# SDRAM.net
KiCad netlist of a schematic drawn in Altium Designer
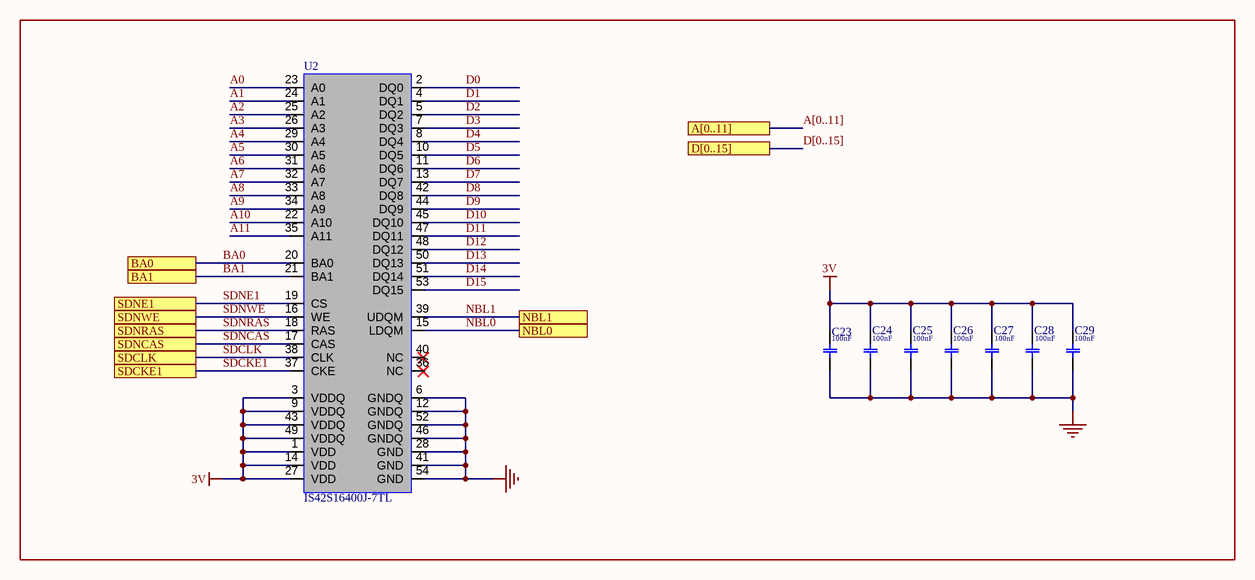
[diagram p0: SDRAM.SchDoc]

(export (version "E")
  (design (tool "Eeschema 10.0.6"))
  (components
    (comp (ref "C23")
      (value "100nF")
      (footprint "CAP-0402")
      (description "Multilayer Ceramic Capacitor, 0.1 uF, 25 V, ± 10%, X7R, 0402 [1005 Metric]")
      (fields
        (field (name "MANUFACTURER") "Yageo")
        (field (name "MANUFACTURER PART NUMBER") "CC0402KRX7R7BB104")
      )
      (libsource (lib "STM32") (part "CAP CER 100nF 16V X7R 0402"))
    )
    (comp (ref "C24")
      (value "100nF")
      (footprint "CAP-0402")
      (description "Multilayer Ceramic Capacitor, 0.1 uF, 25 V, ± 10%, X7R, 0402 [1005 Metric]")
      (fields
        (field (name "MANUFACTURER") "Yageo")
        (field (name "MANUFACTURER PART NUMBER") "CC0402KRX7R7BB104")
      )
      (libsource (lib "STM32") (part "CAP CER 100nF 16V X7R 0402"))
    )
    (comp (ref "C25")
      (value "100nF")
      (footprint "CAP-0402")
      (description "Multilayer Ceramic Capacitor, 0.1 uF, 25 V, ± 10%, X7R, 0402 [1005 Metric]")
      (fields
        (field (name "MANUFACTURER") "Yageo")
        (field (name "MANUFACTURER PART NUMBER") "CC0402KRX7R7BB104")
      )
      (libsource (lib "STM32") (part "CAP CER 100nF 16V X7R 0402"))
    )
    (comp (ref "C26")
      (value "100nF")
      (footprint "CAP-0402")
      (description "Multilayer Ceramic Capacitor, 0.1 uF, 25 V, ± 10%, X7R, 0402 [1005 Metric]")
      (fields
        (field (name "MANUFACTURER") "Yageo")
        (field (name "MANUFACTURER PART NUMBER") "CC0402KRX7R7BB104")
      )
      (libsource (lib "STM32") (part "CAP CER 100nF 16V X7R 0402"))
    )
    (comp (ref "C27")
      (value "100nF")
      (footprint "CAP-0402")
      (description "Multilayer Ceramic Capacitor, 0.1 uF, 25 V, ± 10%, X7R, 0402 [1005 Metric]")
      (fields
        (field (name "MANUFACTURER") "Yageo")
        (field (name "MANUFACTURER PART NUMBER") "CC0402KRX7R7BB104")
      )
      (libsource (lib "STM32") (part "CAP CER 100nF 16V X7R 0402"))
    )
    (comp (ref "C28")
      (value "100nF")
      (footprint "CAP-0402")
      (description "Multilayer Ceramic Capacitor, 0.1 uF, 25 V, ± 10%, X7R, 0402 [1005 Metric]")
      (fields
        (field (name "MANUFACTURER") "Yageo")
        (field (name "MANUFACTURER PART NUMBER") "CC0402KRX7R7BB104")
      )
      (libsource (lib "STM32") (part "CAP CER 100nF 16V X7R 0402"))
    )
    (comp (ref "C29")
      (value "100nF")
      (footprint "CAP-0402")
      (description "Multilayer Ceramic Capacitor, 0.1 uF, 25 V, ± 10%, X7R, 0402 [1005 Metric]")
      (fields
        (field (name "MANUFACTURER") "Yageo")
        (field (name "MANUFACTURER PART NUMBER") "CC0402KRX7R7BB104")
      )
      (libsource (lib "STM32") (part "CAP CER 100nF 16V X7R 0402"))
    )
    (comp (ref "U2")
      (value "IS42S16400J-7TL")
      (footprint "54-TSOP")
      (fields (field (name "MANUFACTURER") "Bel") (field (name "MANUFACTURER PART NUMBER") "0ZCF0200AF2C"))
      (libsource (lib "STM32") (part "IC DRAM 64MBIT PAR 54TSOP II"))
    )
  )
  (nets
    (net (code "1") (name "/A0") (class "Default")
      (node (ref "U2") (pin "23") (pinfunction "A0_23") (pintype "passive"))
    )
    (net (code "2") (name "/A1") (class "Default")
      (node (ref "U2") (pin "24") (pinfunction "A1_24") (pintype "passive"))
    )
    (net (code "3") (name "/A2") (class "Default")
      (node (ref "U2") (pin "25") (pinfunction "A2_25") (pintype "passive"))
    )
    (net (code "4") (name "/A3") (class "Default")
      (node (ref "U2") (pin "26") (pinfunction "A3_26") (pintype "passive"))
    )
    (net (code "5") (name "/A4") (class "Default")
      (node (ref "U2") (pin "29") (pinfunction "A4_29") (pintype "passive"))
    )
    (net (code "6") (name "/A5") (class "Default")
      (node (ref "U2") (pin "30") (pinfunction "A5_30") (pintype "passive"))
    )
    (net (code "7") (name "/A6") (class "Default")
      (node (ref "U2") (pin "31") (pinfunction "A6_31") (pintype "passive"))
    )
    (net (code "8") (name "/A7") (class "Default")
      (node (ref "U2") (pin "32") (pinfunction "A7_32") (pintype "passive"))
    )
    (net (code "9") (name "/A8") (class "Default")
      (node (ref "U2") (pin "33") (pinfunction "A8_33") (pintype "passive"))
    )
    (net (code "10") (name "/A9") (class "Default")
      (node (ref "U2") (pin "34") (pinfunction "A9_34") (pintype "passive"))
    )
    (net (code "11") (name "/A10") (class "Default")
      (node (ref "U2") (pin "22") (pinfunction "A10_22") (pintype "passive"))
    )
    (net (code "12") (name "/A11") (class "Default")
      (node (ref "U2") (pin "35") (pinfunction "A11_35") (pintype "passive"))
    )
    (net (code "14") (name "/BA0") (class "Default")
      (node (ref "U2") (pin "20") (pinfunction "BA0_20") (pintype "passive"))
    )
    (net (code "15") (name "/BA1") (class "Default")
      (node (ref "U2") (pin "21") (pinfunction "BA1_21") (pintype "passive"))
    )
    (net (code "16") (name "/D0") (class "Default")
      (node (ref "U2") (pin "2") (pinfunction "DQ0_2") (pintype "passive"))
    )
    (net (code "17") (name "/D1") (class "Default")
      (node (ref "U2") (pin "4") (pinfunction "DQ1_4") (pintype "passive"))
    )
    (net (code "18") (name "/D2") (class "Default")
      (node (ref "U2") (pin "5") (pinfunction "DQ2_5") (pintype "passive"))
    )
    (net (code "19") (name "/D3") (class "Default")
      (node (ref "U2") (pin "7") (pinfunction "DQ3_7") (pintype "passive"))
    )
    (net (code "20") (name "/D4") (class "Default")
      (node (ref "U2") (pin "8") (pinfunction "DQ4_8") (pintype "passive"))
    )
    (net (code "21") (name "/D5") (class "Default")
      (node (ref "U2") (pin "10") (pinfunction "DQ5_10") (pintype "passive"))
    )
    (net (code "22") (name "/D6") (class "Default")
      (node (ref "U2") (pin "11") (pinfunction "DQ6_11") (pintype "passive"))
    )
    (net (code "23") (name "/D7") (class "Default")
      (node (ref "U2") (pin "13") (pinfunction "DQ7_13") (pintype "passive"))
    )
    (net (code "24") (name "/D8") (class "Default")
      (node (ref "U2") (pin "42") (pinfunction "DQ8_42") (pintype "passive"))
    )
    (net (code "25") (name "/D9") (class "Default")
      (node (ref "U2") (pin "44") (pinfunction "DQ9_44") (pintype "passive"))
    )
    (net (code "26") (name "/D10") (class "Default")
      (node (ref "U2") (pin "45") (pinfunction "DQ10_45") (pintype "passive"))
    )
    (net (code "27") (name "/D11") (class "Default")
      (node (ref "U2") (pin "47") (pinfunction "DQ11_47") (pintype "passive"))
    )
    (net (code "28") (name "/D12") (class "Default")
      (node (ref "U2") (pin "48") (pinfunction "DQ12_48") (pintype "passive"))
    )
    (net (code "29") (name "/D13") (class "Default")
      (node (ref "U2") (pin "50") (pinfunction "DQ13_50") (pintype "passive"))
    )
    (net (code "30") (name "/D14") (class "Default")
      (node (ref "U2") (pin "51") (pinfunction "DQ14_51") (pintype "passive"))
    )
    (net (code "31") (name "/D15") (class "Default")
      (node (ref "U2") (pin "53") (pinfunction "DQ15_53") (pintype "passive"))
    )
    (net (code "33") (name "/NBL0") (class "Default")
      (node (ref "U2") (pin "15") (pinfunction "LDQM_15") (pintype "passive"))
    )
    (net (code "34") (name "/NBL1") (class "Default")
      (node (ref "U2") (pin "39") (pinfunction "UDQM_39") (pintype "passive"))
    )
    (net (code "35") (name "/SDCKE1") (class "Default")
      (node (ref "U2") (pin "37") (pinfunction "CKE_37") (pintype "passive"))
    )
    (net (code "36") (name "/SDCLK") (class "Default")
      (node (ref "U2") (pin "38") (pinfunction "CLK_38") (pintype "passive"))
    )
    (net (code "37") (name "/SDNCAS") (class "Default")
      (node (ref "U2") (pin "17") (pinfunction "CAS_17") (pintype "passive"))
    )
    (net (code "38") (name "/SDNE1") (class "Default")
      (node (ref "U2") (pin "19") (pinfunction "CS_19") (pintype "passive"))
    )
    (net (code "39") (name "/SDNRAS") (class "Default")
      (node (ref "U2") (pin "18") (pinfunction "RAS_18") (pintype "passive"))
    )
    (net (code "40") (name "/SDNWE") (class "Default")
      (node (ref "U2") (pin "16") (pinfunction "WE_16") (pintype "passive"))
    )
    (net (code "41") (name "3V") (class "Default")
      (node (ref "C23") (pin "2") (pinfunction "2_2") (pintype "passive"))
      (node (ref "C24") (pin "2") (pinfunction "2_2") (pintype "passive"))
      (node (ref "C25") (pin "2") (pinfunction "2_2") (pintype "passive"))
      (node (ref "C26") (pin "2") (pinfunction "2_2") (pintype "passive"))
      (node (ref "C27") (pin "2") (pinfunction "2_2") (pintype "passive"))
      (node (ref "C28") (pin "2") (pinfunction "2_2") (pintype "passive"))
      (node (ref "C29") (pin "2") (pinfunction "2_2") (pintype "passive"))
      (node (ref "U2") (pin "1") (pinfunction "VDD_1") (pintype "passive"))
      (node (ref "U2") (pin "14") (pinfunction "VDD_14") (pintype "passive"))
      (node (ref "U2") (pin "27") (pinfunction "VDD_27") (pintype "passive"))
      (node (ref "U2") (pin "3") (pinfunction "VDDQ_3") (pintype "passive"))
      (node (ref "U2") (pin "43") (pinfunction "VDDQ_43") (pintype "passive"))
      (node (ref "U2") (pin "49") (pinfunction "VDDQ_49") (pintype "passive"))
      (node (ref "U2") (pin "9") (pinfunction "VDDQ_9") (pintype "passive"))
    )
    (net (code "42") (name "GND") (class "Default")
      (node (ref "C23") (pin "1") (pinfunction "1_1") (pintype "passive"))
      (node (ref "C24") (pin "1") (pinfunction "1_1") (pintype "passive"))
      (node (ref "C25") (pin "1") (pinfunction "1_1") (pintype "passive"))
      (node (ref "C26") (pin "1") (pinfunction "1_1") (pintype "passive"))
      (node (ref "C27") (pin "1") (pinfunction "1_1") (pintype "passive"))
      (node (ref "C28") (pin "1") (pinfunction "1_1") (pintype "passive"))
      (node (ref "C29") (pin "1") (pinfunction "1_1") (pintype "passive"))
      (node (ref "U2") (pin "12") (pinfunction "GNDQ_12") (pintype "passive"))
      (node (ref "U2") (pin "28") (pinfunction "GND_28") (pintype "passive"))
      (node (ref "U2") (pin "41") (pinfunction "GND_41") (pintype "passive"))
      (node (ref "U2") (pin "46") (pinfunction "GNDQ_46") (pintype "passive"))
      (node (ref "U2") (pin "52") (pinfunction "GNDQ_52") (pintype "passive"))
      (node (ref "U2") (pin "54") (pinfunction "GND_54") (pintype "passive"))
      (node (ref "U2") (pin "6") (pinfunction "GNDQ_6") (pintype "passive"))
    )
    (net (code "43") (name "unconnected-(U2-NC-Pad36)") (class "Default")
      (node (ref "U2") (pin "36") (pinfunction "NC_36") (pintype "passive"))
    )
    (net (code "44") (name "unconnected-(U2-NC-Pad40)") (class "Default")
      (node (ref "U2") (pin "40") (pinfunction "NC_40") (pintype "passive"))
    )
  )
)
